# Cycle-Controller.net
KiCad netlist of a schematic drawn in Altium Designer
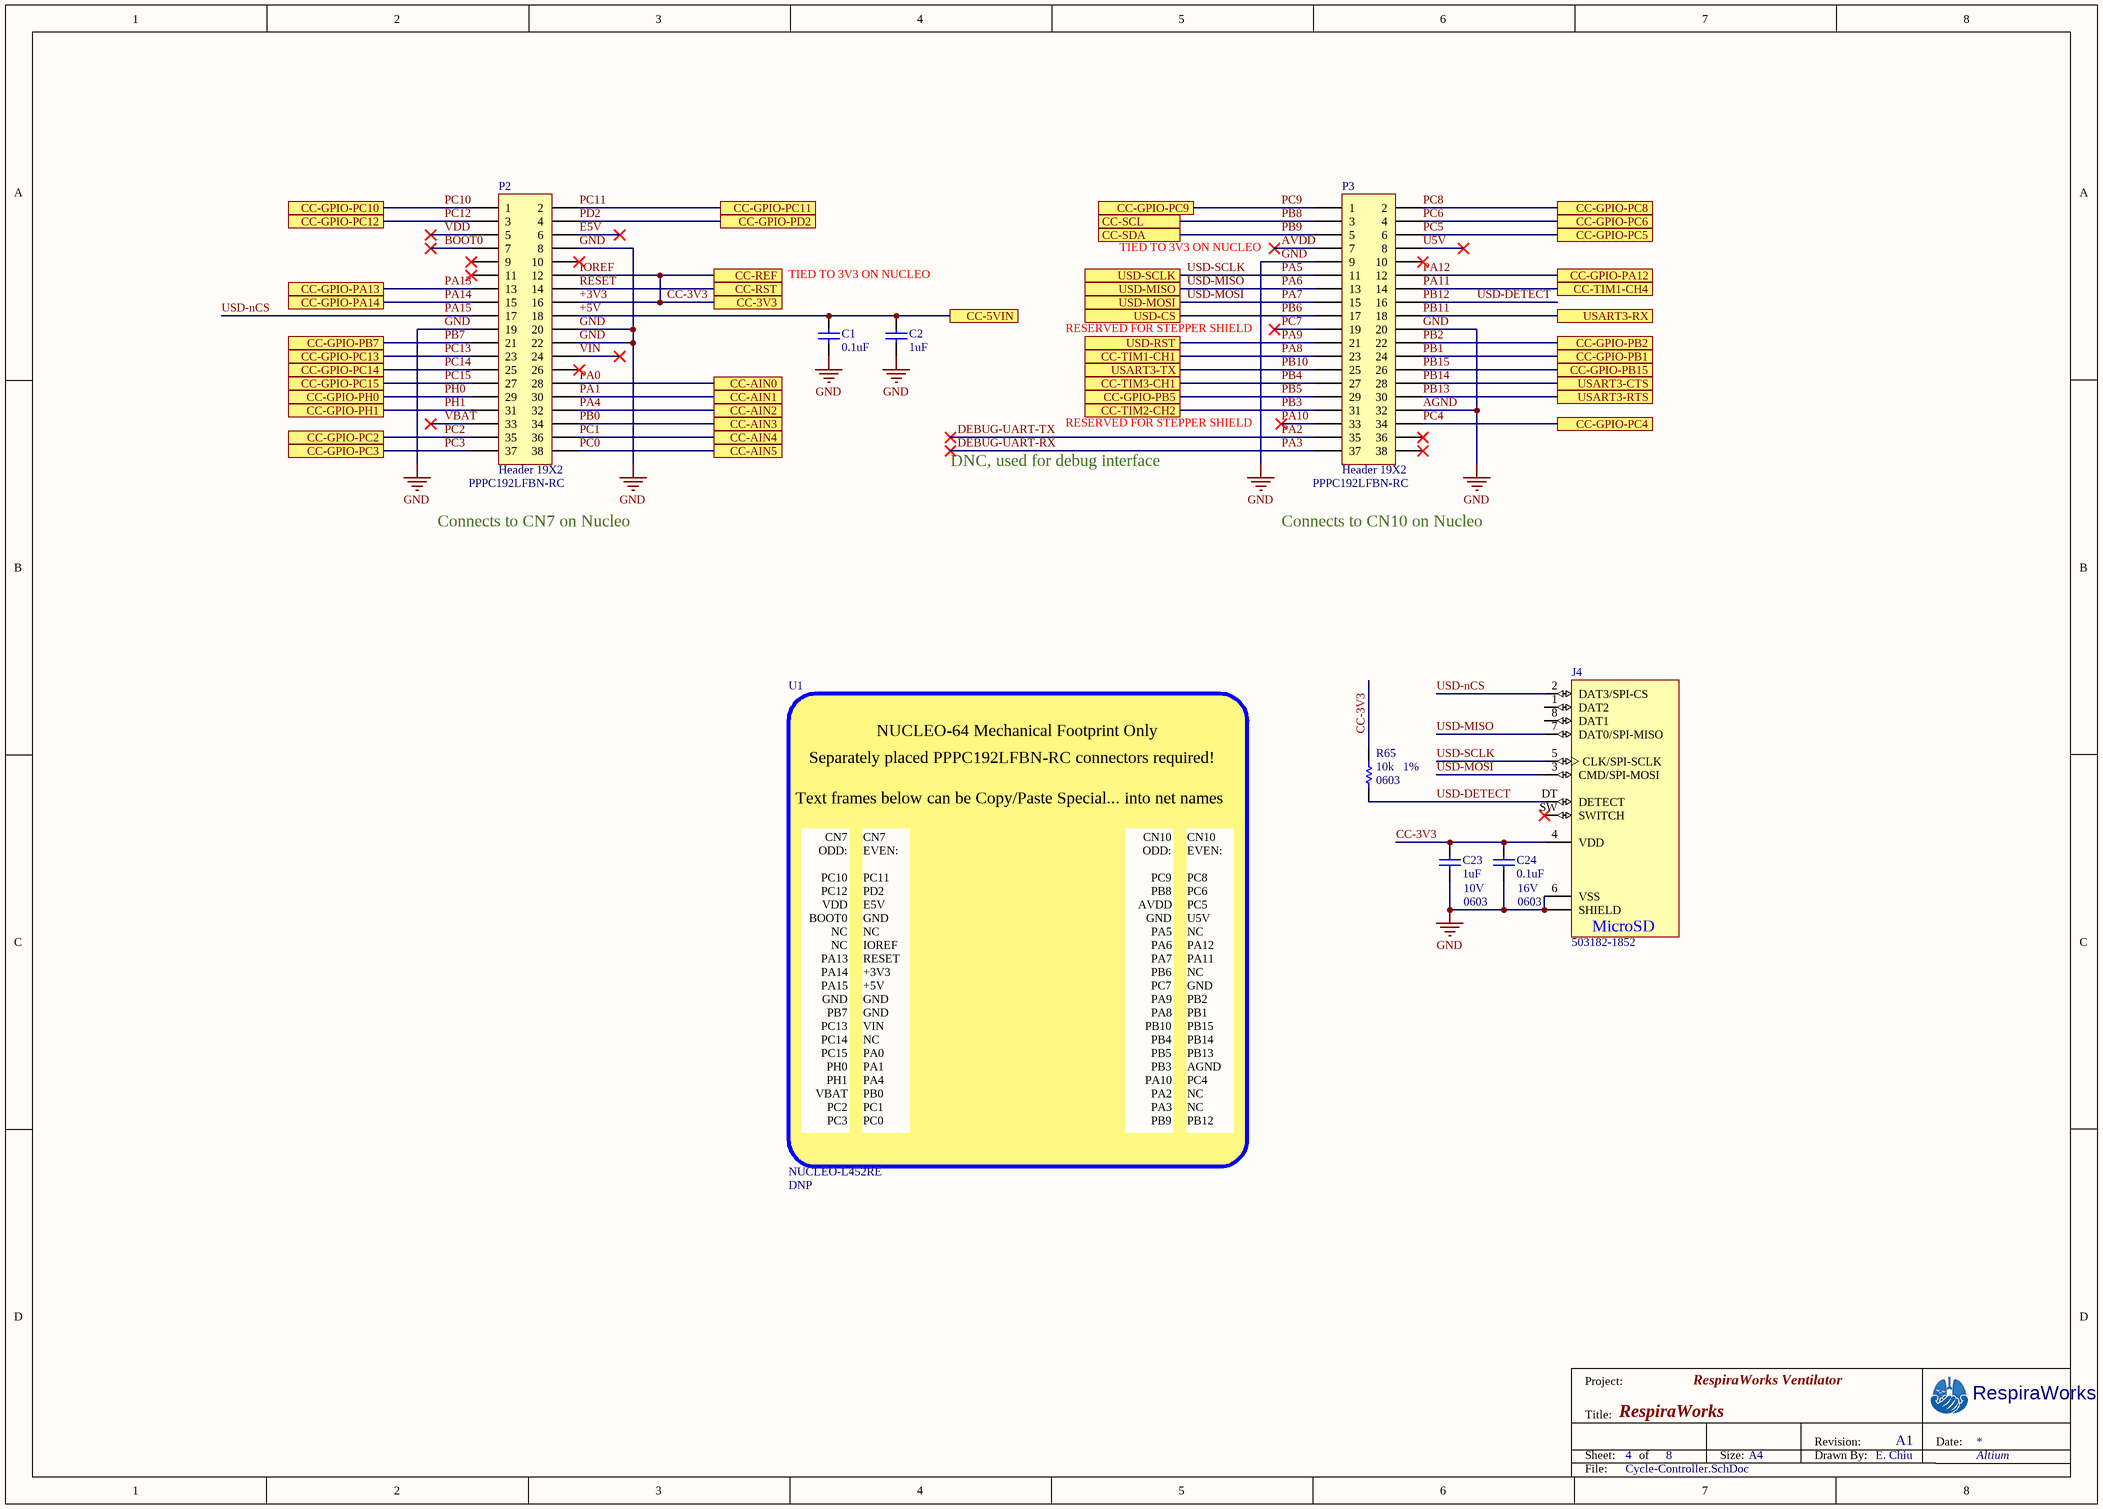
[diagram p0: Cycle-Controller.SchDoc]

(export (version "E")
  (design (tool "Eeschema 10.0.6"))
  (components
    (comp (ref "C1")
      (value "0.1uF")
      (footprint "CAP0603")
      (description "Cap 0603")
      (fields (field (name "MANUFACTURER") "Yageo") (field (name "VOLTAGE") "16V"))
      (libsource (lib "generic") (part "CAP 0603"))
    )
    (comp (ref "C2")
      (value "1uF")
      (footprint "CAP0603")
      (description "Cap 0603")
      (fields (field (name "MANUFACTURER") "Yageo") (field (name "VOLTAGE") "10V"))
      (libsource (lib "generic") (part "CAP 0603"))
    )
    (comp (ref "C23")
      (value "1uF")
      (footprint "CAP0603")
      (description "Cap 0603")
      (fields
        (field (name "MANUFACTURER") "Yageo")
        (field (name "VOLTAGE") "10V")
        (field (name "PCB PACKAGE") "0603")
        (field (name "Comment") "CAP 0603")
      )
      (libsource (lib "generic") (part "CAP 0603"))
    )
    (comp (ref "C24")
      (value "0.1uF")
      (footprint "CAP0603")
      (description "Cap 0603")
      (fields
        (field (name "MANUFACTURER") "Yageo")
        (field (name "VOLTAGE") "16V")
        (field (name "PCB PACKAGE") "0603")
        (field (name "Comment") "CAP 0603")
      )
      (libsource (lib "generic") (part "CAP 0603"))
    )
    (comp (ref "J4")
      (value "503182-1852")
      (footprint "molex:503182-1852")
      (description "10 _8 + 2_ Position Card Connector microSD Surface Mount, Right Angle Gold")
      (fields (field (name "MANUFACTURER") "Molex") (field (name "DIGI-KEY_PART_NUMBER") "WM12834CT-ND"))
      (libsource (lib "molex") (part "503182-1852"))
    )
    (comp (ref "P2")
      (value "Header 19X2")
      (footprint "PPPC192LFBN-RC")
      (description "Female Header, 0.100\" Pitch, 19x2")
      (fields (field (name "MANUFACTURER") "Sullins") (field (name "MANUFACTURER P/N") "PPPC192LFBN-RC"))
      (libsource (lib "sullins") (part "PPPC192LFBN-RC"))
    )
    (comp (ref "P3")
      (value "Header 19X2")
      (footprint "PPPC192LFBN-RC")
      (description "Female Header, 0.100\" Pitch, 19x2")
      (fields (field (name "MANUFACTURER") "Sullins") (field (name "MANUFACTURER P/N") "PPPC192LFBN-RC"))
      (libsource (lib "sullins") (part "PPPC192LFBN-RC"))
    )
    (comp (ref "R65")
      (value "10k")
      (footprint "RES0603")
      (description "Res 0603")
      (fields
        (field (name "MANUFACTURER") "Panasonic")
        (field (name "PCB PACKAGE") "0603")
        (field (name "TOLERANCE") "1%")
        (field (name "Comment") "RES 0603")
      )
      (libsource (lib "generic") (part "RES 0603"))
    )
    (comp (ref "U1")
      (value "NUCLEO-L452RE")
      (footprint "NUCLEO-64")
      (description "STM32F446RE Nucleo MCU Board")
      (fields (field (name "MANUFACTURER") "ST") (field (name "DO NOT POPULATE") "DNP"))
      (libsource (lib "st") (part "NUCLEO-L452RE"))
    )
  )
  (nets
    (net (code "1") (name "/+3V3") (class "Default")
      (node (ref "C23") (pin "1") (pinfunction "1_1") (pintype "passive"))
      (node (ref "C24") (pin "1") (pinfunction "1_1") (pintype "passive"))
      (node (ref "J4") (pin "4") (pinfunction "VDD_4") (pintype "power_in"))
      (node (ref "P2") (pin "12") (pinfunction "12_12") (pintype "passive"))
      (node (ref "P2") (pin "16") (pinfunction "16_16") (pintype "passive"))
      (node (ref "R65") (pin "2") (pinfunction "2_2") (pintype "passive"))
    )
    (net (code "2") (name "/+5V") (class "Default")
      (node (ref "C1") (pin "1") (pinfunction "1_1") (pintype "passive"))
      (node (ref "C2") (pin "1") (pinfunction "1_1") (pintype "passive"))
      (node (ref "P2") (pin "18") (pinfunction "18_18") (pintype "passive"))
    )
    (net (code "3") (name "/AVDD") (class "Default")
      (node (ref "P3") (pin "7") (pinfunction "7_7") (pintype "passive+no_connect"))
    )
    (net (code "4") (name "/BOOT0") (class "Default")
      (node (ref "P2") (pin "7") (pinfunction "7_7") (pintype "passive+no_connect"))
    )
    (net (code "5") (name "/DEBUG-UART-RX") (class "Default")
      (node (ref "P3") (pin "37") (pinfunction "37_37") (pintype "passive+no_connect"))
    )
    (net (code "6") (name "/DEBUG-UART-TX") (class "Default")
      (node (ref "P3") (pin "35") (pinfunction "35_35") (pintype "passive+no_connect"))
    )
    (net (code "7") (name "/E5V") (class "Default")
      (node (ref "P2") (pin "6") (pinfunction "6_6") (pintype "passive+no_connect"))
    )
    (net (code "8") (name "/PA0") (class "Default")
      (node (ref "P2") (pin "28") (pinfunction "28_28") (pintype "passive"))
    )
    (net (code "9") (name "/PA1") (class "Default")
      (node (ref "P2") (pin "30") (pinfunction "30_30") (pintype "passive"))
    )
    (net (code "10") (name "/PA4") (class "Default")
      (node (ref "P2") (pin "32") (pinfunction "32_32") (pintype "passive"))
    )
    (net (code "11") (name "/PA5") (class "Default")
      (node (ref "J4") (pin "5") (pinfunction "CLK/SPI-SCLK_5") (pintype "bidirectional"))
      (node (ref "P3") (pin "11") (pinfunction "11_11") (pintype "passive"))
    )
    (net (code "12") (name "/PA6") (class "Default")
      (node (ref "J4") (pin "7") (pinfunction "DAT0/SPI-MISO_7") (pintype "bidirectional"))
      (node (ref "P3") (pin "13") (pinfunction "13_13") (pintype "passive"))
    )
    (net (code "13") (name "/PA7") (class "Default")
      (node (ref "J4") (pin "3") (pinfunction "CMD/SPI-MOSI_3") (pintype "bidirectional"))
      (node (ref "P3") (pin "15") (pinfunction "15_15") (pintype "passive"))
    )
    (net (code "14") (name "/PA8") (class "Default")
      (node (ref "P3") (pin "23") (pinfunction "23_23") (pintype "passive"))
    )
    (net (code "15") (name "/PA9") (class "Default")
      (node (ref "P3") (pin "21") (pinfunction "21_21") (pintype "passive"))
    )
    (net (code "16") (name "/PA10") (class "Default")
      (node (ref "P3") (pin "33") (pinfunction "33_33") (pintype "passive+no_connect"))
    )
    (net (code "17") (name "/PA11") (class "Default")
      (node (ref "P3") (pin "14") (pinfunction "14_14") (pintype "passive"))
    )
    (net (code "18") (name "/PA12") (class "Default")
      (node (ref "P3") (pin "12") (pinfunction "12_12") (pintype "passive"))
    )
    (net (code "19") (name "/PA13") (class "Default")
      (node (ref "P2") (pin "13") (pinfunction "13_13") (pintype "passive"))
    )
    (net (code "20") (name "/PA14") (class "Default")
      (node (ref "P2") (pin "15") (pinfunction "15_15") (pintype "passive"))
    )
    (net (code "21") (name "/PA15") (class "Default")
      (node (ref "J4") (pin "2") (pinfunction "DAT3/SPI-CS_2") (pintype "bidirectional"))
      (node (ref "P2") (pin "17") (pinfunction "17_17") (pintype "passive"))
    )
    (net (code "22") (name "/PB0") (class "Default")
      (node (ref "P2") (pin "34") (pinfunction "34_34") (pintype "passive"))
    )
    (net (code "23") (name "/PB1") (class "Default")
      (node (ref "P3") (pin "24") (pinfunction "24_24") (pintype "passive"))
    )
    (net (code "24") (name "/PB2") (class "Default")
      (node (ref "P3") (pin "22") (pinfunction "22_22") (pintype "passive"))
    )
    (net (code "25") (name "/PB3") (class "Default")
      (node (ref "P3") (pin "31") (pinfunction "31_31") (pintype "passive"))
    )
    (net (code "26") (name "/PB4") (class "Default")
      (node (ref "P3") (pin "27") (pinfunction "27_27") (pintype "passive"))
    )
    (net (code "27") (name "/PB5") (class "Default")
      (node (ref "P3") (pin "29") (pinfunction "29_29") (pintype "passive"))
    )
    (net (code "28") (name "/PB6") (class "Default")
      (node (ref "P3") (pin "17") (pinfunction "17_17") (pintype "passive"))
    )
    (net (code "29") (name "/PB7") (class "Default")
      (node (ref "P2") (pin "21") (pinfunction "21_21") (pintype "passive"))
    )
    (net (code "30") (name "/PB8") (class "Default")
      (node (ref "P3") (pin "3") (pinfunction "3_3") (pintype "passive"))
    )
    (net (code "31") (name "/PB9") (class "Default")
      (node (ref "P3") (pin "5") (pinfunction "5_5") (pintype "passive"))
    )
    (net (code "32") (name "/PB10") (class "Default")
      (node (ref "P3") (pin "25") (pinfunction "25_25") (pintype "passive"))
    )
    (net (code "33") (name "/PB11") (class "Default")
      (node (ref "P3") (pin "18") (pinfunction "18_18") (pintype "passive"))
    )
    (net (code "34") (name "/PB12") (class "Default")
      (node (ref "J4") (pin "DT") (pinfunction "DETECT_DT") (pintype "bidirectional"))
      (node (ref "P3") (pin "16") (pinfunction "16_16") (pintype "passive"))
      (node (ref "R65") (pin "1") (pinfunction "1_1") (pintype "passive"))
    )
    (net (code "35") (name "/PB13") (class "Default")
      (node (ref "P3") (pin "30") (pinfunction "30_30") (pintype "passive"))
    )
    (net (code "36") (name "/PB14") (class "Default")
      (node (ref "P3") (pin "28") (pinfunction "28_28") (pintype "passive"))
    )
    (net (code "37") (name "/PB15") (class "Default")
      (node (ref "P3") (pin "26") (pinfunction "26_26") (pintype "passive"))
    )
    (net (code "38") (name "/PC0") (class "Default")
      (node (ref "P2") (pin "38") (pinfunction "38_38") (pintype "passive"))
    )
    (net (code "39") (name "/PC1") (class "Default")
      (node (ref "P2") (pin "36") (pinfunction "36_36") (pintype "passive"))
    )
    (net (code "40") (name "/PC2") (class "Default")
      (node (ref "P2") (pin "35") (pinfunction "35_35") (pintype "passive"))
    )
    (net (code "41") (name "/PC3") (class "Default")
      (node (ref "P2") (pin "37") (pinfunction "37_37") (pintype "passive"))
    )
    (net (code "42") (name "/PC4") (class "Default")
      (node (ref "P3") (pin "34") (pinfunction "34_34") (pintype "passive"))
    )
    (net (code "43") (name "/PC5") (class "Default")
      (node (ref "P3") (pin "6") (pinfunction "6_6") (pintype "passive"))
    )
    (net (code "44") (name "/PC6") (class "Default")
      (node (ref "P3") (pin "4") (pinfunction "4_4") (pintype "passive"))
    )
    (net (code "45") (name "/PC7") (class "Default")
      (node (ref "P3") (pin "19") (pinfunction "19_19") (pintype "passive+no_connect"))
    )
    (net (code "46") (name "/PC8") (class "Default")
      (node (ref "P3") (pin "2") (pinfunction "2_2") (pintype "passive"))
    )
    (net (code "47") (name "/PC9") (class "Default")
      (node (ref "P3") (pin "1") (pinfunction "1_1") (pintype "passive"))
    )
    (net (code "48") (name "/PC10") (class "Default")
      (node (ref "P2") (pin "1") (pinfunction "1_1") (pintype "passive"))
    )
    (net (code "49") (name "/PC11") (class "Default")
      (node (ref "P2") (pin "2") (pinfunction "2_2") (pintype "passive"))
    )
    (net (code "50") (name "/PC12") (class "Default")
      (node (ref "P2") (pin "3") (pinfunction "3_3") (pintype "passive"))
    )
    (net (code "51") (name "/PC13") (class "Default")
      (node (ref "P2") (pin "23") (pinfunction "23_23") (pintype "passive"))
    )
    (net (code "52") (name "/PC14") (class "Default")
      (node (ref "P2") (pin "25") (pinfunction "25_25") (pintype "passive"))
    )
    (net (code "53") (name "/PC15") (class "Default")
      (node (ref "P2") (pin "27") (pinfunction "27_27") (pintype "passive"))
    )
    (net (code "54") (name "/PD2") (class "Default")
      (node (ref "P2") (pin "4") (pinfunction "4_4") (pintype "passive"))
    )
    (net (code "55") (name "/PH0") (class "Default")
      (node (ref "P2") (pin "29") (pinfunction "29_29") (pintype "passive"))
    )
    (net (code "56") (name "/PH1") (class "Default")
      (node (ref "P2") (pin "31") (pinfunction "31_31") (pintype "passive"))
    )
    (net (code "57") (name "/RESET") (class "Default")
      (node (ref "P2") (pin "14") (pinfunction "14_14") (pintype "passive"))
    )
    (net (code "58") (name "/U5V") (class "Default")
      (node (ref "P3") (pin "8") (pinfunction "8_8") (pintype "passive+no_connect"))
    )
    (net (code "59") (name "/VBAT") (class "Default")
      (node (ref "P2") (pin "33") (pinfunction "33_33") (pintype "passive+no_connect"))
    )
    (net (code "60") (name "/VDD") (class "Default")
      (node (ref "P2") (pin "5") (pinfunction "5_5") (pintype "passive+no_connect"))
    )
    (net (code "61") (name "/VIN") (class "Default")
      (node (ref "P2") (pin "24") (pinfunction "24_24") (pintype "passive+no_connect"))
    )
    (net (code "62") (name "GND") (class "Default")
      (node (ref "C1") (pin "2") (pinfunction "2_2") (pintype "passive"))
      (node (ref "C2") (pin "2") (pinfunction "2_2") (pintype "passive"))
      (node (ref "C23") (pin "2") (pinfunction "2_2") (pintype "passive"))
      (node (ref "C24") (pin "2") (pinfunction "2_2") (pintype "passive"))
      (node (ref "J4") (pin "6") (pinfunction "VSS_6") (pintype "power_in"))
      (node (ref "J4") (pin "P1") (pinfunction "SHIELD_P1") (pintype "passive"))
      (node (ref "J4") (pin "P2") (pinfunction "SHIELD_P2") (pintype "passive"))
      (node (ref "J4") (pin "P3") (pinfunction "SHIELD_P3") (pintype "passive"))
      (node (ref "J4") (pin "P4") (pinfunction "SHIELD_P4") (pintype "passive"))
      (node (ref "J4") (pin "P5") (pinfunction "SHIELD_P5") (pintype "passive"))
      (node (ref "P2") (pin "19") (pinfunction "19_19") (pintype "passive"))
      (node (ref "P2") (pin "20") (pinfunction "20_20") (pintype "passive"))
      (node (ref "P2") (pin "22") (pinfunction "22_22") (pintype "passive"))
      (node (ref "P2") (pin "8") (pinfunction "8_8") (pintype "passive"))
      (node (ref "P3") (pin "20") (pinfunction "20_20") (pintype "passive"))
      (node (ref "P3") (pin "32") (pinfunction "32_32") (pintype "passive"))
      (node (ref "P3") (pin "9") (pinfunction "9_9") (pintype "passive"))
    )
    (net (code "63") (name "unconnected-(J4-DAT1-Pad8)") (class "Default")
      (node (ref "J4") (pin "8") (pinfunction "DAT1_8") (pintype "bidirectional"))
    )
    (net (code "64") (name "unconnected-(J4-DAT2-Pad1)") (class "Default")
      (node (ref "J4") (pin "1") (pinfunction "DAT2_1") (pintype "bidirectional"))
    )
    (net (code "65") (name "unconnected-(J4-SWITCH-PadSW)") (class "Default")
      (node (ref "J4") (pin "SW") (pinfunction "SWITCH_SW") (pintype "bidirectional+no_connect"))
    )
    (net (code "66") (name "unconnected-(P2-Pad9)") (class "Default")
      (node (ref "P2") (pin "9") (pinfunction "9_9") (pintype "passive+no_connect"))
    )
    (net (code "67") (name "unconnected-(P2-Pad10)") (class "Default")
      (node (ref "P2") (pin "10") (pinfunction "10_10") (pintype "passive+no_connect"))
    )
    (net (code "68") (name "unconnected-(P2-Pad11)") (class "Default")
      (node (ref "P2") (pin "11") (pinfunction "11_11") (pintype "passive+no_connect"))
    )
    (net (code "69") (name "unconnected-(P2-Pad26)") (class "Default")
      (node (ref "P2") (pin "26") (pinfunction "26_26") (pintype "passive+no_connect"))
    )
    (net (code "70") (name "unconnected-(P3-Pad10)") (class "Default")
      (node (ref "P3") (pin "10") (pinfunction "10_10") (pintype "passive+no_connect"))
    )
    (net (code "71") (name "unconnected-(P3-Pad36)") (class "Default")
      (node (ref "P3") (pin "36") (pinfunction "36_36") (pintype "passive+no_connect"))
    )
    (net (code "72") (name "unconnected-(P3-Pad38)") (class "Default")
      (node (ref "P3") (pin "38") (pinfunction "38_38") (pintype "passive+no_connect"))
    )
  )
)
